# rpi900.net
KiCad netlist of a schematic drawn in EAGLE
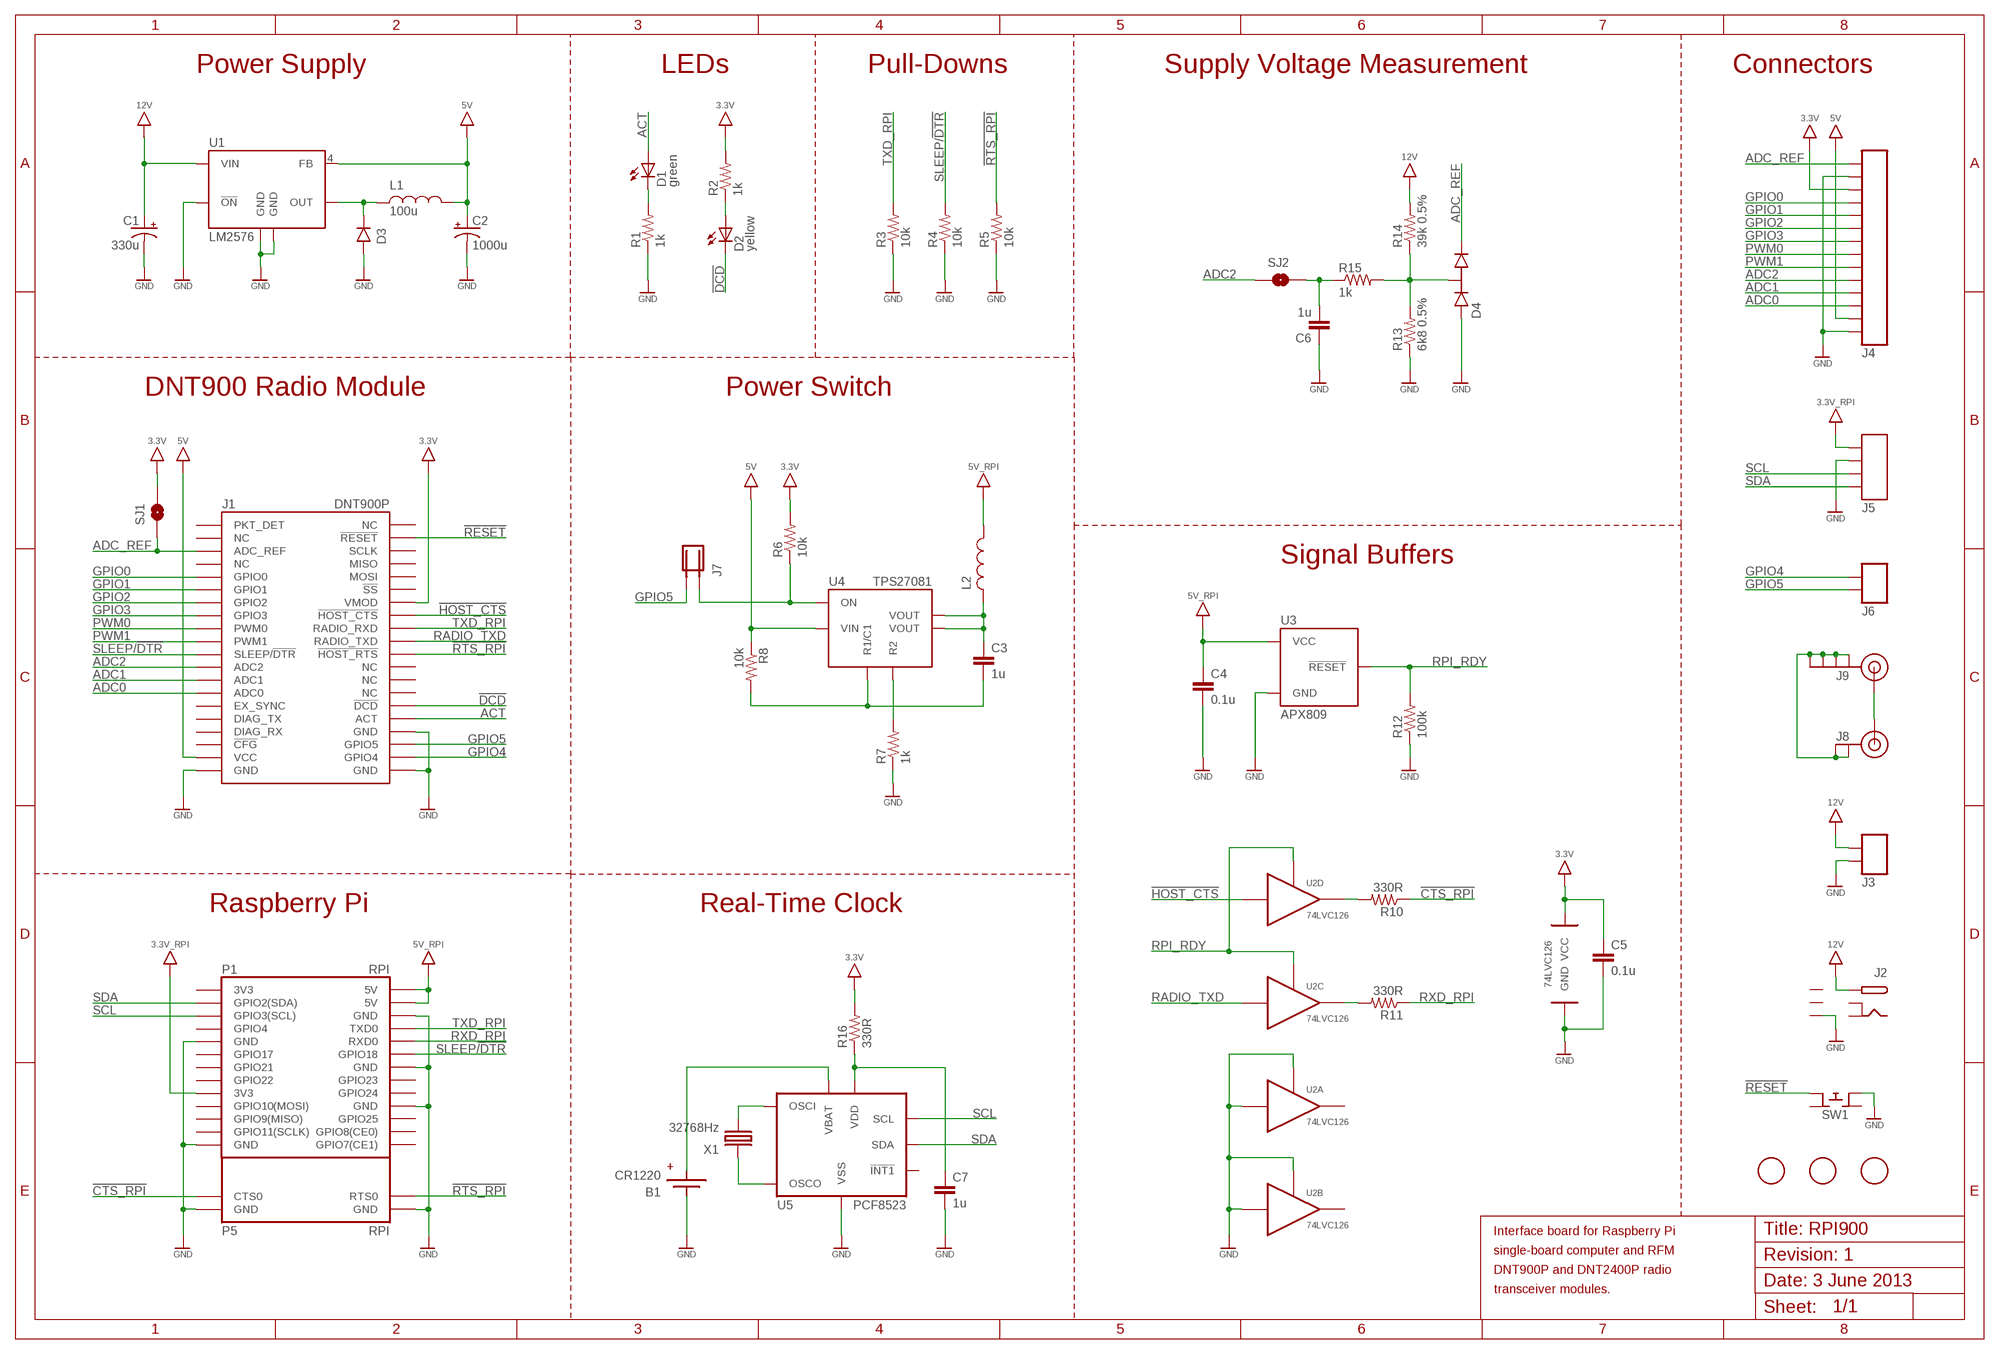
[diagram p0: schematic, sheet 1]

(export (version "E")
  (design (tool "Eeschema 10.0.6"))
  (components
    (comp (ref "B1")
      (value "CR1220")
      (footprint "eagle-import:3000")
      (libsource (lib "eagle-import") (part "CR1220SMDR"))
    )
    (comp (ref "C1")
      (value "330u")
      (footprint "eagle-import:140CLH-1010")
      (libsource (lib "eagle-import") (part "CAP_POL-SMD"))
    )
    (comp (ref "C2")
      (value "1000u")
      (footprint "eagle-import:140CLH-1010")
      (libsource (lib "eagle-import") (part "CAP_POL-SMD"))
    )
    (comp (ref "C3")
      (value "1u")
      (footprint "eagle-import:0805")
      (libsource (lib "eagle-import") (part "CAP"))
    )
    (comp (ref "C4")
      (value "0.1u")
      (footprint "eagle-import:0805")
      (libsource (lib "eagle-import") (part "CAP"))
    )
    (comp (ref "C5")
      (value "0.1u")
      (footprint "eagle-import:0805")
      (libsource (lib "eagle-import") (part "CAP"))
    )
    (comp (ref "C6")
      (value "1u")
      (footprint "eagle-import:0805")
      (libsource (lib "eagle-import") (part "CAP"))
    )
    (comp (ref "C7")
      (value "1u")
      (footprint "eagle-import:0805")
      (libsource (lib "eagle-import") (part "CAP"))
    )
    (comp (ref "D1")
      (value "green")
      (footprint "eagle-import:0805-LED")
      (libsource (lib "eagle-import") (part "LTST-C171KGKT"))
    )
    (comp (ref "D2")
      (value "yellow")
      (footprint "eagle-import:0805-LED")
      (libsource (lib "eagle-import") (part "LTST-C171KGKT"))
    )
    (comp (ref "D3")
      (value "MURS320T3G")
      (footprint "eagle-import:DO-214AB")
      (libsource (lib "eagle-import") (part "MURS320T3G"))
    )
    (comp (ref "D4")
      (value "BAT54S")
      (footprint "eagle-import:SOT23")
      (libsource (lib "eagle-import") (part "BAT54S"))
    )
    (comp (ref "F1")
      (value "FIDUCIAL")
      (footprint "eagle-import:FIDUCIAL_1MM")
      (libsource (lib "eagle-import") (part "FIDUCIAL"))
    )
    (comp (ref "F2")
      (value "FIDUCIAL")
      (footprint "eagle-import:FIDUCIAL_1MM")
      (libsource (lib "eagle-import") (part "FIDUCIAL"))
    )
    (comp (ref "F3")
      (value "FIDUCIAL")
      (footprint "eagle-import:FIDUCIAL_1MM")
      (libsource (lib "eagle-import") (part "FIDUCIAL"))
    )
    (comp (ref "J1")
      (value "DNT900P")
      (footprint "eagle-import:DNT900P")
      (libsource (lib "eagle-import") (part "DNT900P"))
    )
    (comp (ref "J2")
      (value "DCBARRELPTH")
      (footprint "eagle-import:PJ-002A")
      (libsource (lib "eagle-import") (part "DCBARRELPTH"))
    )
    (comp (ref "J3")
      (value "TERMINAL-2P-3.5MM")
      (footprint "eagle-import:TERMINAL-2P-3.5MM")
      (libsource (lib "eagle-import") (part "TERMINAL-2P-3.5MM"))
    )
    (comp (ref "J4")
      (value "TERMINAL-14P")
      (footprint "eagle-import:TERMINAL-14P-0.1")
      (libsource (lib "eagle-import") (part "TERMINAL-14P"))
    )
    (comp (ref "J5")
      (value "TERMINAL-4P")
      (footprint "eagle-import:TERMINAL-4P-0.1")
      (libsource (lib "eagle-import") (part "TERMINAL-4P"))
    )
    (comp (ref "J6")
      (value "TERMINAL-2P-0.1")
      (footprint "eagle-import:TERMINAL-2P-0.1")
      (libsource (lib "eagle-import") (part "TERMINAL-2P-0.1"))
    )
    (comp (ref "J7")
      (value "JUMPER")
      (footprint "eagle-import:JUMPER")
      (libsource (lib "eagle-import") (part "JUMPER"))
    )
    (comp (ref "J8")
      (value "U.FL")
      (footprint "eagle-import:U.FL")
      (libsource (lib "eagle-import") (part "U.FL"))
    )
    (comp (ref "J9")
      (value "SMAPTH")
      (footprint "eagle-import:SMA-PTH")
      (libsource (lib "eagle-import") (part "SMAPTH"))
    )
    (comp (ref "L1")
      (value "100u")
      (footprint "eagle-import:SRR1280")
      (libsource (lib "eagle-import") (part "SRR1280"))
    )
    (comp (ref "L2")
      (value "FERRITE-BEAD")
      (footprint "eagle-import:0805")
      (libsource (lib "eagle-import") (part "FERRITE-BEAD"))
    )
    (comp (ref "P")
      (value "RPI")
      (footprint "eagle-import:RPI")
      (libsource (lib "eagle-import") (part "RPI"))
    )
    (comp (ref "R1")
      (value "1k")
      (footprint "eagle-import:0805")
      (libsource (lib "eagle-import") (part "RESISTOR"))
    )
    (comp (ref "R2")
      (value "1k")
      (footprint "eagle-import:0805")
      (libsource (lib "eagle-import") (part "RESISTOR"))
    )
    (comp (ref "R3")
      (value "10k")
      (footprint "eagle-import:0805")
      (libsource (lib "eagle-import") (part "RESISTOR"))
    )
    (comp (ref "R4")
      (value "10k")
      (footprint "eagle-import:0805")
      (libsource (lib "eagle-import") (part "RESISTOR"))
    )
    (comp (ref "R5")
      (value "10k")
      (footprint "eagle-import:0805")
      (libsource (lib "eagle-import") (part "RESISTOR"))
    )
    (comp (ref "R6")
      (value "10k")
      (footprint "eagle-import:0805")
      (libsource (lib "eagle-import") (part "RESISTOR"))
    )
    (comp (ref "R7")
      (value "1k")
      (footprint "eagle-import:0805")
      (libsource (lib "eagle-import") (part "RESISTOR"))
    )
    (comp (ref "R8")
      (value "10k")
      (footprint "eagle-import:0805")
      (libsource (lib "eagle-import") (part "RESISTOR"))
    )
    (comp (ref "R10")
      (value "330R")
      (footprint "eagle-import:0805")
      (libsource (lib "eagle-import") (part "RESISTOR"))
    )
    (comp (ref "R11")
      (value "330R")
      (footprint "eagle-import:0805")
      (libsource (lib "eagle-import") (part "RESISTOR"))
    )
    (comp (ref "R12")
      (value "100k")
      (footprint "eagle-import:0805")
      (libsource (lib "eagle-import") (part "RESISTOR"))
    )
    (comp (ref "R13")
      (value "6k8 0.5%")
      (footprint "eagle-import:0805")
      (libsource (lib "eagle-import") (part "RESISTOR"))
    )
    (comp (ref "R14")
      (value "39k 0.5%")
      (footprint "eagle-import:0805")
      (libsource (lib "eagle-import") (part "RESISTOR"))
    )
    (comp (ref "R15")
      (value "1k")
      (footprint "eagle-import:0805")
      (libsource (lib "eagle-import") (part "RESISTOR"))
    )
    (comp (ref "R16")
      (value "330R")
      (footprint "eagle-import:0805")
      (libsource (lib "eagle-import") (part "RESISTOR"))
    )
    (comp (ref "SJ1")
      (value "SOLDERJUMPERTRACE")
      (footprint "eagle-import:SJ_2S-TRACE")
      (libsource (lib "eagle-import") (part "SOLDERJUMPERTRACE"))
    )
    (comp (ref "SJ2")
      (value "SOLDERJUMPERNO")
      (footprint "eagle-import:SJ_2S-NO")
      (libsource (lib "eagle-import") (part "SOLDERJUMPERNO"))
    )
    (comp (ref "SW1")
      (value "FSM4JH")
      (footprint "eagle-import:JSM4JH")
      (libsource (lib "eagle-import") (part "FSM4JH"))
    )
    (comp (ref "U1")
      (value "LM2576")
      (footprint "eagle-import:TO-263")
      (libsource (lib "eagle-import") (part "LM2576"))
    )
    (comp (ref "U2")
      (value "74LVC126")
      (footprint "eagle-import:SO14")
      (libsource (lib "eagle-import") (part "74LVC126"))
    )
    (comp (ref "U3")
      (value "APX809")
      (footprint "eagle-import:SOT23")
      (libsource (lib "eagle-import") (part "APX809"))
    )
    (comp (ref "U4")
      (value "TPS27081")
      (footprint "eagle-import:TSOT-23-6")
      (libsource (lib "eagle-import") (part "TPS27081"))
    )
    (comp (ref "U5")
      (value "PCF8523")
      (footprint "eagle-import:SO08")
      (libsource (lib "eagle-import") (part "PCF8523"))
    )
    (comp (ref "X1")
      (value "32768Hz")
      (footprint "eagle-import:CFS-206")
      (libsource (lib "eagle-import") (part "XTAL6MM"))
    )
  )
  (nets
    (net (code "1") (name "/3V3") (class "Default")
      (node (ref "P") (pin "P$1") (pinfunction "3V3_P$1") (pintype "power_in"))
    )
    (net (code "2") (name "/ACT") (class "Default")
      (node (ref "D1") (pin "A") (pinfunction "A_A") (pintype "passive"))
      (node (ref "J1") (pin "P$25") (pinfunction "ACT_P$25") (pintype "output"))
    )
    (net (code "3") (name "/ADC0") (class "Default")
      (node (ref "J1") (pin "P$14") (pinfunction "ADC0_P$14") (pintype "input"))
      (node (ref "J4") (pin "12") (pinfunction "P$12_12") (pintype "bidirectional"))
    )
    (net (code "4") (name "/ADC1") (class "Default")
      (node (ref "J1") (pin "P$13") (pinfunction "ADC1_P$13") (pintype "input"))
      (node (ref "J4") (pin "11") (pinfunction "P$11_11") (pintype "bidirectional"))
    )
    (net (code "5") (name "/ADC2") (class "Default")
      (node (ref "J1") (pin "P$12") (pinfunction "ADC2_P$12") (pintype "input"))
      (node (ref "J4") (pin "10") (pinfunction "P$10_10") (pintype "bidirectional"))
      (node (ref "SJ2") (pin "1") (pinfunction "1_1") (pintype "passive"))
    )
    (net (code "6") (name "/ADC_REF") (class "Default")
      (node (ref "D4") (pin "P$2") (pinfunction "P$2_P$2") (pintype "passive"))
      (node (ref "J1") (pin "P$3") (pinfunction "ADC_REF_P$3") (pintype "input"))
      (node (ref "J4") (pin "1") (pinfunction "P$1_1") (pintype "bidirectional"))
      (node (ref "SJ1") (pin "1") (pinfunction "1_1") (pintype "passive"))
    )
    (net (code "7") (name "/CENTRE-BOTTOM") (class "Default")
      (node (ref "J2") (pin "CENTRE-BOTTOM") (pinfunction "CENTRE-BOTTOM_CENTRE-BOTTOM") (pintype "power_in"))
    )
    (net (code "8") (name "/GPIO0") (class "Default")
      (node (ref "J1") (pin "P$5") (pinfunction "GPIO0_P$5") (pintype "bidirectional"))
      (node (ref "J4") (pin "4") (pinfunction "P$4_4") (pintype "bidirectional"))
    )
    (net (code "9") (name "/GPIO1") (class "Default")
      (node (ref "J1") (pin "P$6") (pinfunction "GPIO1_P$6") (pintype "bidirectional"))
      (node (ref "J4") (pin "5") (pinfunction "P$5_5") (pintype "bidirectional"))
    )
    (net (code "10") (name "/GPIO2") (class "Default")
      (node (ref "J1") (pin "P$7") (pinfunction "GPIO2_P$7") (pintype "bidirectional"))
      (node (ref "J4") (pin "6") (pinfunction "P$6_6") (pintype "bidirectional"))
    )
    (net (code "11") (name "/GPIO3") (class "Default")
      (node (ref "J1") (pin "P$8") (pinfunction "GPIO3_P$8") (pintype "bidirectional"))
      (node (ref "J4") (pin "7") (pinfunction "P$7_7") (pintype "bidirectional"))
    )
    (net (code "12") (name "/GPIO4") (class "Default")
      (node (ref "J1") (pin "P$22") (pinfunction "GPIO4_P$22") (pintype "bidirectional"))
      (node (ref "J6") (pin "1") (pinfunction "P$1_1") (pintype "bidirectional"))
    )
    (net (code "13") (name "/GPIO5") (class "Default")
      (node (ref "J1") (pin "P$23") (pinfunction "GPIO5_P$23") (pintype "bidirectional"))
      (node (ref "J6") (pin "2") (pinfunction "P$2_2") (pintype "bidirectional"))
      (node (ref "J7") (pin "2") (pinfunction "P$2_2") (pintype "passive"))
    )
    (net (code "14") (name "/PWM0") (class "Default")
      (node (ref "J1") (pin "P$9") (pinfunction "PWM0_P$9") (pintype "output"))
      (node (ref "J4") (pin "8") (pinfunction "P$8_8") (pintype "bidirectional"))
    )
    (net (code "15") (name "/PWM1") (class "Default")
      (node (ref "J1") (pin "P$10") (pinfunction "PWM1_P$10") (pintype "output"))
      (node (ref "J4") (pin "9") (pinfunction "P$9_9") (pintype "bidirectional"))
    )
    (net (code "16") (name "/RADIO_TXD") (class "Default")
      (node (ref "J1") (pin "P$31") (pinfunction "RADIO_TXD_P$31") (pintype "output"))
      (node (ref "U2") (pin "9") (pinfunction "X_9") (pintype "input"))
    )
    (net (code "17") (name "/RPI_RDY") (class "Default")
      (node (ref "R12") (pin "2") (pinfunction "2_2") (pintype "passive"))
      (node (ref "U2") (pin "10") (pinfunction "~{OE}_10") (pintype "input"))
      (node (ref "U2") (pin "13") (pinfunction "~{OE}_13") (pintype "input"))
      (node (ref "U3") (pin "P$2") (pinfunction "~{RESET}_P$2") (pintype "output"))
    )
    (net (code "18") (name "/RXD_RPI") (class "Default")
      (node (ref "P") (pin "P$10") (pinfunction "RXD0_P$10") (pintype "bidirectional"))
      (node (ref "R11") (pin "1") (pinfunction "1_1") (pintype "passive"))
    )
    (net (code "19") (name "/SCL") (class "Default")
      (node (ref "J5") (pin "3") (pinfunction "3_3") (pintype "bidirectional"))
      (node (ref "P") (pin "P$5") (pinfunction "GPIO3(SCL)_P$5") (pintype "bidirectional"))
      (node (ref "U5") (pin "6") (pinfunction "SCL_6") (pintype "input"))
    )
    (net (code "20") (name "/SDA") (class "Default")
      (node (ref "J5") (pin "4") (pinfunction "4_4") (pintype "bidirectional"))
      (node (ref "P") (pin "P$3") (pinfunction "GPIO2(SDA)_P$3") (pintype "bidirectional"))
      (node (ref "U5") (pin "5") (pinfunction "SDA_5") (pintype "bidirectional"))
    )
    (net (code "21") (name "/SHUNT") (class "Default")
      (node (ref "J2") (pin "SHUNT") (pinfunction "SHUNT_SHUNT") (pintype "power_in"))
    )
    (net (code "22") (name "/SHUNT-BOTTOM") (class "Default")
      (node (ref "J2") (pin "SHUNT-BOTTOM") (pinfunction "SHUNT-BOTTOM_SHUNT-BOTTOM") (pintype "power_in"))
    )
    (net (code "23") (name "/SLEEP{slash}~{DTR}") (class "Default")
      (node (ref "J1") (pin "P$11") (pinfunction "SLEEP/~{DTR}_P$11") (pintype "input"))
      (node (ref "P") (pin "P$12") (pinfunction "GPIO18_P$12") (pintype "bidirectional"))
      (node (ref "R4") (pin "2") (pinfunction "2_2") (pintype "passive"))
    )
    (net (code "24") (name "/SLEEVE") (class "Default")
      (node (ref "J2") (pin "SLEEVE") (pinfunction "SLEEVE_SLEEVE") (pintype "power_in"))
    )
    (net (code "25") (name "/TXD_RPI") (class "Default")
      (node (ref "J1") (pin "P$32") (pinfunction "RADIO_RXD_P$32") (pintype "input"))
      (node (ref "P") (pin "P$8") (pinfunction "TXD0_P$8") (pintype "bidirectional"))
      (node (ref "R3") (pin "2") (pinfunction "2_2") (pintype "passive"))
    )
    (net (code "26") (name "/~{CTS_RPI}") (class "Default")
      (node (ref "P") (pin "P$31") (pinfunction "CTS0_P$31") (pintype "bidirectional"))
      (node (ref "R10") (pin "1") (pinfunction "1_1") (pintype "passive"))
    )
    (net (code "27") (name "/~{DCD}") (class "Default")
      (node (ref "D2") (pin "K") (pinfunction "C_K") (pintype "passive"))
      (node (ref "J1") (pin "P$26") (pinfunction "~{DCD}_P$26") (pintype "output"))
    )
    (net (code "28") (name "/~{HOST_CTS}") (class "Default")
      (node (ref "J1") (pin "P$33") (pinfunction "~{HOST_CTS}_P$33") (pintype "output"))
      (node (ref "U2") (pin "12") (pinfunction "X_12") (pintype "input"))
    )
    (net (code "29") (name "/~{RESET}") (class "Default")
      (node (ref "J1") (pin "P$39") (pinfunction "~{RESET}_P$39") (pintype "input"))
      (node (ref "SW1") (pin "P$3") (pinfunction "3_P$3") (pintype "passive"))
    )
    (net (code "30") (name "/~{RTS_RPI}") (class "Default")
      (node (ref "J1") (pin "P$30") (pinfunction "~{HOST_RTS}_P$30") (pintype "input"))
      (node (ref "P") (pin "P$32") (pinfunction "RTS0_P$32") (pintype "bidirectional"))
      (node (ref "R5") (pin "2") (pinfunction "2_2") (pintype "passive"))
    )
    (net (code "31") (name "3.3V") (class "Default")
      (node (ref "C5") (pin "1") (pinfunction "1_1") (pintype "passive"))
      (node (ref "J1") (pin "P$34") (pinfunction "VMOD_P$34") (pintype "power_in"))
      (node (ref "J4") (pin "3") (pinfunction "P$3_3") (pintype "bidirectional"))
      (node (ref "R16") (pin "2") (pinfunction "2_2") (pintype "passive"))
      (node (ref "R2") (pin "2") (pinfunction "2_2") (pintype "passive"))
      (node (ref "R6") (pin "2") (pinfunction "2_2") (pintype "passive"))
      (node (ref "SJ1") (pin "2") (pinfunction "2_2") (pintype "passive"))
      (node (ref "U2") (pin "14") (pinfunction "VCC_14") (pintype "power_in"))
    )
    (net (code "32") (name "3.3V_RPI") (class "Default")
      (node (ref "J5") (pin "1") (pinfunction "1_1") (pintype "bidirectional"))
      (node (ref "P") (pin "P$17") (pinfunction "3V3_P$17") (pintype "power_in"))
    )
    (net (code "33") (name "5V") (class "Default")
      (node (ref "C2") (pin "+") (pinfunction "+_+") (pintype "passive"))
      (node (ref "J1") (pin "P$19") (pinfunction "VCC_P$19") (pintype "power_in"))
      (node (ref "J4") (pin "13") (pinfunction "P$13_13") (pintype "bidirectional"))
      (node (ref "L1") (pin "P$2") (pinfunction "P$2_P$2") (pintype "passive"))
      (node (ref "R8") (pin "1") (pinfunction "1_1") (pintype "passive"))
      (node (ref "U1") (pin "4") (pinfunction "FB_4") (pintype "passive"))
      (node (ref "U4") (pin "P$4") (pinfunction "VIN_P$4") (pintype "power_in"))
    )
    (net (code "34") (name "5V_RPI") (class "Default")
      (node (ref "C4") (pin "1") (pinfunction "1_1") (pintype "passive"))
      (node (ref "L2") (pin "2") (pinfunction "P$2_2") (pintype "passive"))
      (node (ref "P") (pin "P$2") (pinfunction "5V_P$2") (pintype "power_in"))
      (node (ref "P") (pin "P$4") (pinfunction "5V_P$4") (pintype "power_in"))
      (node (ref "U3") (pin "P$3") (pinfunction "VCC_P$3") (pintype "power_in"))
    )
    (net (code "35") (name "12V") (class "Default")
      (node (ref "C1") (pin "+") (pinfunction "+_+") (pintype "passive"))
      (node (ref "J2") (pin "CENTRE") (pinfunction "CENTRE_CENTRE") (pintype "power_in"))
      (node (ref "J3") (pin "P$1") (pinfunction "P$1_P$1") (pintype "bidirectional"))
      (node (ref "R14") (pin "2") (pinfunction "2_2") (pintype "passive"))
      (node (ref "U1") (pin "1") (pinfunction "VIN_1") (pintype "power_in"))
    )
    (net (code "36") (name "GND") (class "Default")
      (node (ref "B1") (pin "NEGATIVE") (pinfunction "NEGATIVE_NEGATIVE") (pintype "power_in"))
      (node (ref "C1") (pin "-") (pinfunction "-_-") (pintype "passive"))
      (node (ref "C2") (pin "-") (pinfunction "-_-") (pintype "passive"))
      (node (ref "C4") (pin "2") (pinfunction "2_2") (pintype "passive"))
      (node (ref "C5") (pin "2") (pinfunction "2_2") (pintype "passive"))
      (node (ref "C6") (pin "1") (pinfunction "1_1") (pintype "passive"))
      (node (ref "C7") (pin "2") (pinfunction "2_2") (pintype "passive"))
      (node (ref "D3") (pin "A") (pinfunction "A_A") (pintype "passive"))
      (node (ref "D4") (pin "P$1") (pinfunction "P$1_P$1") (pintype "passive"))
      (node (ref "J1") (pin "P$20") (pinfunction "GND_P$20") (pintype "power_in"))
      (node (ref "J1") (pin "P$21") (pinfunction "GND_P$21") (pintype "power_in"))
      (node (ref "J1") (pin "P$24") (pinfunction "GND_P$24") (pintype "power_in"))
      (node (ref "J2") (pin "SLEEVE-BOTTOM") (pinfunction "SLEEVE-BOTTOM_SLEEVE-BOTTOM") (pintype "power_in"))
      (node (ref "J3") (pin "P$2") (pinfunction "P$2_P$2") (pintype "bidirectional"))
      (node (ref "J4") (pin "14") (pinfunction "P$14_14") (pintype "bidirectional"))
      (node (ref "J4") (pin "2") (pinfunction "P$2_2") (pintype "bidirectional"))
      (node (ref "J5") (pin "2") (pinfunction "2_2") (pintype "bidirectional"))
      (node (ref "P") (pin "P$14") (pinfunction "GND_P$14") (pintype "power_in"))
      (node (ref "P") (pin "P$20") (pinfunction "GND_P$20") (pintype "power_in"))
      (node (ref "P") (pin "P$25") (pinfunction "GND_P$25") (pintype "power_in"))
      (node (ref "P") (pin "P$33") (pinfunction "GND_P$33") (pintype "power_in"))
      (node (ref "P") (pin "P$34") (pinfunction "GND_P$34") (pintype "power_in"))
      (node (ref "P") (pin "P$6") (pinfunction "GND_P$6") (pintype "power_in"))
      (node (ref "P") (pin "P$9") (pinfunction "GND_P$9") (pintype "power_in"))
      (node (ref "R1") (pin "1") (pinfunction "1_1") (pintype "passive"))
      (node (ref "R12") (pin "1") (pinfunction "1_1") (pintype "passive"))
      (node (ref "R13") (pin "1") (pinfunction "1_1") (pintype "passive"))
      (node (ref "R3") (pin "1") (pinfunction "1_1") (pintype "passive"))
      (node (ref "R4") (pin "1") (pinfunction "1_1") (pintype "passive"))
      (node (ref "R5") (pin "1") (pinfunction "1_1") (pintype "passive"))
      (node (ref "R7") (pin "1") (pinfunction "1_1") (pintype "passive"))
      (node (ref "SW1") (pin "P$1") (pinfunction "1_P$1") (pintype "passive"))
      (node (ref "U1") (pin "3") (pinfunction "GND_3") (pintype "power_in"))
      (node (ref "U1") (pin "5") (pinfunction "~{ON}_5") (pintype "input"))
      (node (ref "U1") (pin "TAB") (pinfunction "GND_TAB") (pintype "power_in"))
      (node (ref "U2") (pin "1") (pinfunction "~{OE}_1") (pintype "input"))
      (node (ref "U2") (pin "2") (pinfunction "X_2") (pintype "input"))
      (node (ref "U2") (pin "4") (pinfunction "~{OE}_4") (pintype "input"))
      (node (ref "U2") (pin "5") (pinfunction "X_5") (pintype "input"))
      (node (ref "U2") (pin "7") (pinfunction "GND_7") (pintype "power_in"))
      (node (ref "U3") (pin "P$1") (pinfunction "GND_P$1") (pintype "power_in"))
      (node (ref "U5") (pin "4") (pinfunction "VSS_4") (pintype "power_in"))
    )
    (net (code "37") (name "Net-(B1-POSITIVE)") (class "Default")
      (node (ref "B1") (pin "POSITIVE1") (pinfunction "POSITIVE_POSITIVE1") (pintype "power_in"))
      (node (ref "U5") (pin "3") (pinfunction "VBAT_3") (pintype "power_in"))
    )
    (net (code "38") (name "Net-(C6-Pad2)") (class "Default")
      (node (ref "C6") (pin "2") (pinfunction "2_2") (pintype "passive"))
      (node (ref "R15") (pin "1") (pinfunction "1_1") (pintype "passive"))
      (node (ref "SJ2") (pin "2") (pinfunction "2_2") (pintype "passive"))
    )
    (net (code "39") (name "Net-(D1-C)") (class "Default")
      (node (ref "D1") (pin "K") (pinfunction "C_K") (pintype "passive"))
      (node (ref "R1") (pin "2") (pinfunction "2_2") (pintype "passive"))
    )
    (net (code "40") (name "Net-(D2-PadA)") (class "Default")
      (node (ref "D2") (pin "A") (pinfunction "A_A") (pintype "passive"))
      (node (ref "R2") (pin "1") (pinfunction "1_1") (pintype "passive"))
    )
    (net (code "41") (name "Net-(D4-PadP$3)") (class "Default")
      (node (ref "D4") (pin "P$3") (pinfunction "P$3_P$3") (pintype "passive"))
      (node (ref "R13") (pin "2") (pinfunction "2_2") (pintype "passive"))
      (node (ref "R14") (pin "1") (pinfunction "1_1") (pintype "passive"))
      (node (ref "R15") (pin "2") (pinfunction "2_2") (pintype "passive"))
    )
    (net (code "42") (name "Net-(J7-P$1)") (class "Default")
      (node (ref "J7") (pin "1") (pinfunction "P$1_1") (pintype "passive"))
      (node (ref "R6") (pin "1") (pinfunction "1_1") (pintype "passive"))
      (node (ref "U4") (pin "P$5") (pinfunction "ON_P$5") (pintype "input"))
    )
    (net (code "43") (name "Net-(J8-GND-PadP$1)") (class "Default")
      (node (ref "J8") (pin "P$1") (pinfunction "GND_P$1") (pintype "bidirectional"))
      (node (ref "J8") (pin "P$2") (pinfunction "GND_P$2") (pintype "bidirectional"))
      (node (ref "J9") (pin "GND@0") (pinfunction "GND_GND@0") (pintype "bidirectional"))
      (node (ref "J9") (pin "GND@1") (pinfunction "GND_GND@1") (pintype "bidirectional"))
      (node (ref "J9") (pin "GND@2") (pinfunction "GND_GND@2") (pintype "bidirectional"))
      (node (ref "J9") (pin "GND@3") (pinfunction "GND_GND@3") (pintype "bidirectional"))
    )
    (net (code "44") (name "Net-(J8-SIGNAL)") (class "Default")
      (node (ref "J8") (pin "P$3") (pinfunction "SIGNAL_P$3") (pintype "bidirectional"))
      (node (ref "J9") (pin "SIG") (pinfunction "SIGNAL_SIG") (pintype "bidirectional"))
    )
    (net (code "45") (name "Net-(L2-P$1)") (class "Default")
      (node (ref "C3") (pin "1") (pinfunction "1_1") (pintype "passive"))
      (node (ref "L2") (pin "1") (pinfunction "P$1_1") (pintype "passive"))
      (node (ref "U4") (pin "P$2") (pinfunction "VOUT_P$2") (pintype "power_in"))
      (node (ref "U4") (pin "P$3") (pinfunction "VOUT_P$3") (pintype "power_in"))
    )
    (net (code "46") (name "Net-(U1-OUT)") (class "Default")
      (node (ref "D3") (pin "K") (pinfunction "K_K") (pintype "passive"))
      (node (ref "L1") (pin "P$1") (pinfunction "P$1_P$1") (pintype "passive"))
      (node (ref "U1") (pin "2") (pinfunction "OUT_2") (pintype "passive"))
    )
    (net (code "47") (name "Net-(U2C-Y)") (class "Default")
      (node (ref "R11") (pin "2") (pinfunction "2_2") (pintype "passive"))
      (node (ref "U2") (pin "8") (pinfunction "Y_8") (pintype "output"))
    )
    (net (code "48") (name "Net-(U2D-Y)") (class "Default")
      (node (ref "R10") (pin "2") (pinfunction "2_2") (pintype "passive"))
      (node (ref "U2") (pin "11") (pinfunction "Y_11") (pintype "output"))
    )
    (net (code "49") (name "Net-(U4-R1{slash}C1)") (class "Default")
      (node (ref "C3") (pin "2") (pinfunction "2_2") (pintype "passive"))
      (node (ref "R8") (pin "2") (pinfunction "2_2") (pintype "passive"))
      (node (ref "U4") (pin "P$6") (pinfunction "R1/C1_P$6") (pintype "power_in"))
    )
    (net (code "50") (name "Net-(U4-R2)") (class "Default")
      (node (ref "R7") (pin "2") (pinfunction "2_2") (pintype "passive"))
      (node (ref "U4") (pin "P$1") (pinfunction "R2_P$1") (pintype "passive"))
    )
    (net (code "51") (name "Net-(U5-OSCI)") (class "Default")
      (node (ref "U5") (pin "1") (pinfunction "OSCI_1") (pintype "passive"))
      (node (ref "X1") (pin "P$2") (pinfunction "P$2_P$2") (pintype "passive"))
    )
    (net (code "52") (name "Net-(U5-OSCO)") (class "Default")
      (node (ref "U5") (pin "2") (pinfunction "OSCO_2") (pintype "passive"))
      (node (ref "X1") (pin "P$1") (pinfunction "P$1_P$1") (pintype "passive"))
    )
    (net (code "53") (name "Net-(U5-VDD)") (class "Default")
      (node (ref "C7") (pin "1") (pinfunction "1_1") (pintype "passive"))
      (node (ref "R16") (pin "1") (pinfunction "1_1") (pintype "passive"))
      (node (ref "U5") (pin "8") (pinfunction "VDD_8") (pintype "power_in"))
    )
    (net (code "54") (name "unconnected-(J1-DIAG_RX-PadP$17)") (class "Default")
      (node (ref "J1") (pin "P$17") (pinfunction "DIAG_RX_P$17") (pintype "input"))
    )
    (net (code "55") (name "unconnected-(J1-DIAG_TX-PadP$16)") (class "Default")
      (node (ref "J1") (pin "P$16") (pinfunction "DIAG_TX_P$16") (pintype "output"))
    )
    (net (code "56") (name "unconnected-(J1-EX_SYNC-PadP$15)") (class "Default")
      (node (ref "J1") (pin "P$15") (pinfunction "EX_SYNC_P$15") (pintype "input"))
    )
    (net (code "57") (name "unconnected-(J1-MISO-PadP$37)") (class "Default")
      (node (ref "J1") (pin "P$37") (pinfunction "MISO_P$37") (pintype "bidirectional"))
    )
    (net (code "58") (name "unconnected-(J1-MOSI-PadP$36)") (class "Default")
      (node (ref "J1") (pin "P$36") (pinfunction "MOSI_P$36") (pintype "bidirectional"))
    )
    (net (code "59") (name "unconnected-(J1-NC-PadP$2)") (class "Default")
      (node (ref "J1") (pin "P$2") (pinfunction "NC_P$2") (pintype "no_connect"))
    )
    (net (code "60") (name "unconnected-(J1-NC-PadP$4)") (class "Default")
      (node (ref "J1") (pin "P$4") (pinfunction "NC_P$4") (pintype "no_connect"))
    )
    (net (code "61") (name "unconnected-(J1-NC-PadP$27)") (class "Default")
      (node (ref "J1") (pin "P$27") (pinfunction "NC_P$27") (pintype "no_connect"))
    )
    (net (code "62") (name "unconnected-(J1-NC-PadP$28)") (class "Default")
      (node (ref "J1") (pin "P$28") (pinfunction "NC_P$28") (pintype "no_connect"))
    )
    (net (code "63") (name "unconnected-(J1-NC-PadP$29)") (class "Default")
      (node (ref "J1") (pin "P$29") (pinfunction "NC_P$29") (pintype "no_connect"))
    )
    (net (code "64") (name "unconnected-(J1-NC-PadP$40)") (class "Default")
      (node (ref "J1") (pin "P$40") (pinfunction "NC_P$40") (pintype "no_connect"))
    )
    (net (code "65") (name "unconnected-(J1-PKT_DET-PadP$1)") (class "Default")
      (node (ref "J1") (pin "P$1") (pinfunction "PKT_DET_P$1") (pintype "output"))
    )
    (net (code "66") (name "unconnected-(J1-SCLK-PadP$38)") (class "Default")
      (node (ref "J1") (pin "P$38") (pinfunction "SCLK_P$38") (pintype "bidirectional"))
    )
    (net (code "67") (name "unconnected-(J1-~{CFG}-PadP$18)") (class "Default")
      (node (ref "J1") (pin "P$18") (pinfunction "~{CFG}_P$18") (pintype "input"))
    )
    (net (code "68") (name "unconnected-(J1-~{SS}-PadP$35)") (class "Default")
      (node (ref "J1") (pin "P$35") (pinfunction "~{SS}_P$35") (pintype "input"))
    )
    (net (code "69") (name "unconnected-(PA-GPIO4-PadP$7)") (class "Default")
      (node (ref "P") (pin "P$7") (pinfunction "GPIO4_P$7") (pintype "bidirectional"))
    )
    (net (code "70") (name "unconnected-(PA-GPIO7(CE1)-PadP$26)") (class "Default")
      (node (ref "P") (pin "P$26") (pinfunction "GPIO7(CE1)_P$26") (pintype "bidirectional"))
    )
    (net (code "71") (name "unconnected-(PA-GPIO8(CE0)-PadP$24)") (class "Default")
      (node (ref "P") (pin "P$24") (pinfunction "GPIO8(CE0)_P$24") (pintype "bidirectional"))
    )
    (net (code "72") (name "unconnected-(PA-GPIO9(MISO)-PadP$21)") (class "Default")
      (node (ref "P") (pin "P$21") (pinfunction "GPIO9(MISO)_P$21") (pintype "bidirectional"))
    )
    (net (code "73") (name "unconnected-(PA-GPIO10(MOSI)-PadP$19)") (class "Default")
      (node (ref "P") (pin "P$19") (pinfunction "GPIO10(MOSI)_P$19") (pintype "bidirectional"))
    )
    (net (code "74") (name "unconnected-(PA-GPIO11(SCLK)-PadP$23)") (class "Default")
      (node (ref "P") (pin "P$23") (pinfunction "GPIO11(SCLK)_P$23") (pintype "bidirectional"))
    )
    (net (code "75") (name "unconnected-(PA-GPIO17-PadP$11)") (class "Default")
      (node (ref "P") (pin "P$11") (pinfunction "GPIO17_P$11") (pintype "bidirectional"))
    )
    (net (code "76") (name "unconnected-(PA-GPIO21-PadP$13)") (class "Default")
      (node (ref "P") (pin "P$13") (pinfunction "GPIO21_P$13") (pintype "bidirectional"))
    )
    (net (code "77") (name "unconnected-(PA-GPIO22-PadP$15)") (class "Default")
      (node (ref "P") (pin "P$15") (pinfunction "GPIO22_P$15") (pintype "bidirectional"))
    )
    (net (code "78") (name "unconnected-(PA-GPIO23-PadP$16)") (class "Default")
      (node (ref "P") (pin "P$16") (pinfunction "GPIO23_P$16") (pintype "bidirectional"))
    )
    (net (code "79") (name "unconnected-(PA-GPIO24-PadP$18)") (class "Default")
      (node (ref "P") (pin "P$18") (pinfunction "GPIO24_P$18") (pintype "bidirectional"))
    )
    (net (code "80") (name "unconnected-(PA-GPIO25-PadP$22)") (class "Default")
      (node (ref "P") (pin "P$22") (pinfunction "GPIO25_P$22") (pintype "bidirectional"))
    )
    (net (code "81") (name "unconnected-(SW1-2-PadP$2)") (class "Default")
      (node (ref "SW1") (pin "P$2") (pinfunction "2_P$2") (pintype "passive"))
    )
    (net (code "82") (name "unconnected-(SW1-4-PadP$4)") (class "Default")
      (node (ref "SW1") (pin "P$4") (pinfunction "4_P$4") (pintype "passive"))
    )
    (net (code "83") (name "unconnected-(U2A-Y-Pad3)") (class "Default")
      (node (ref "U2") (pin "3") (pinfunction "Y_3") (pintype "output"))
    )
    (net (code "84") (name "unconnected-(U2B-Y-Pad6)") (class "Default")
      (node (ref "U2") (pin "6") (pinfunction "Y_6") (pintype "output"))
    )
    (net (code "85") (name "unconnected-(U5-~{INT1}-Pad7)") (class "Default")
      (node (ref "U5") (pin "7") (pinfunction "~{INT1}_7") (pintype "output"))
    )
  )
)
